# Induction_motor_control.net
KiCad netlist of a schematic drawn in EasyEDA
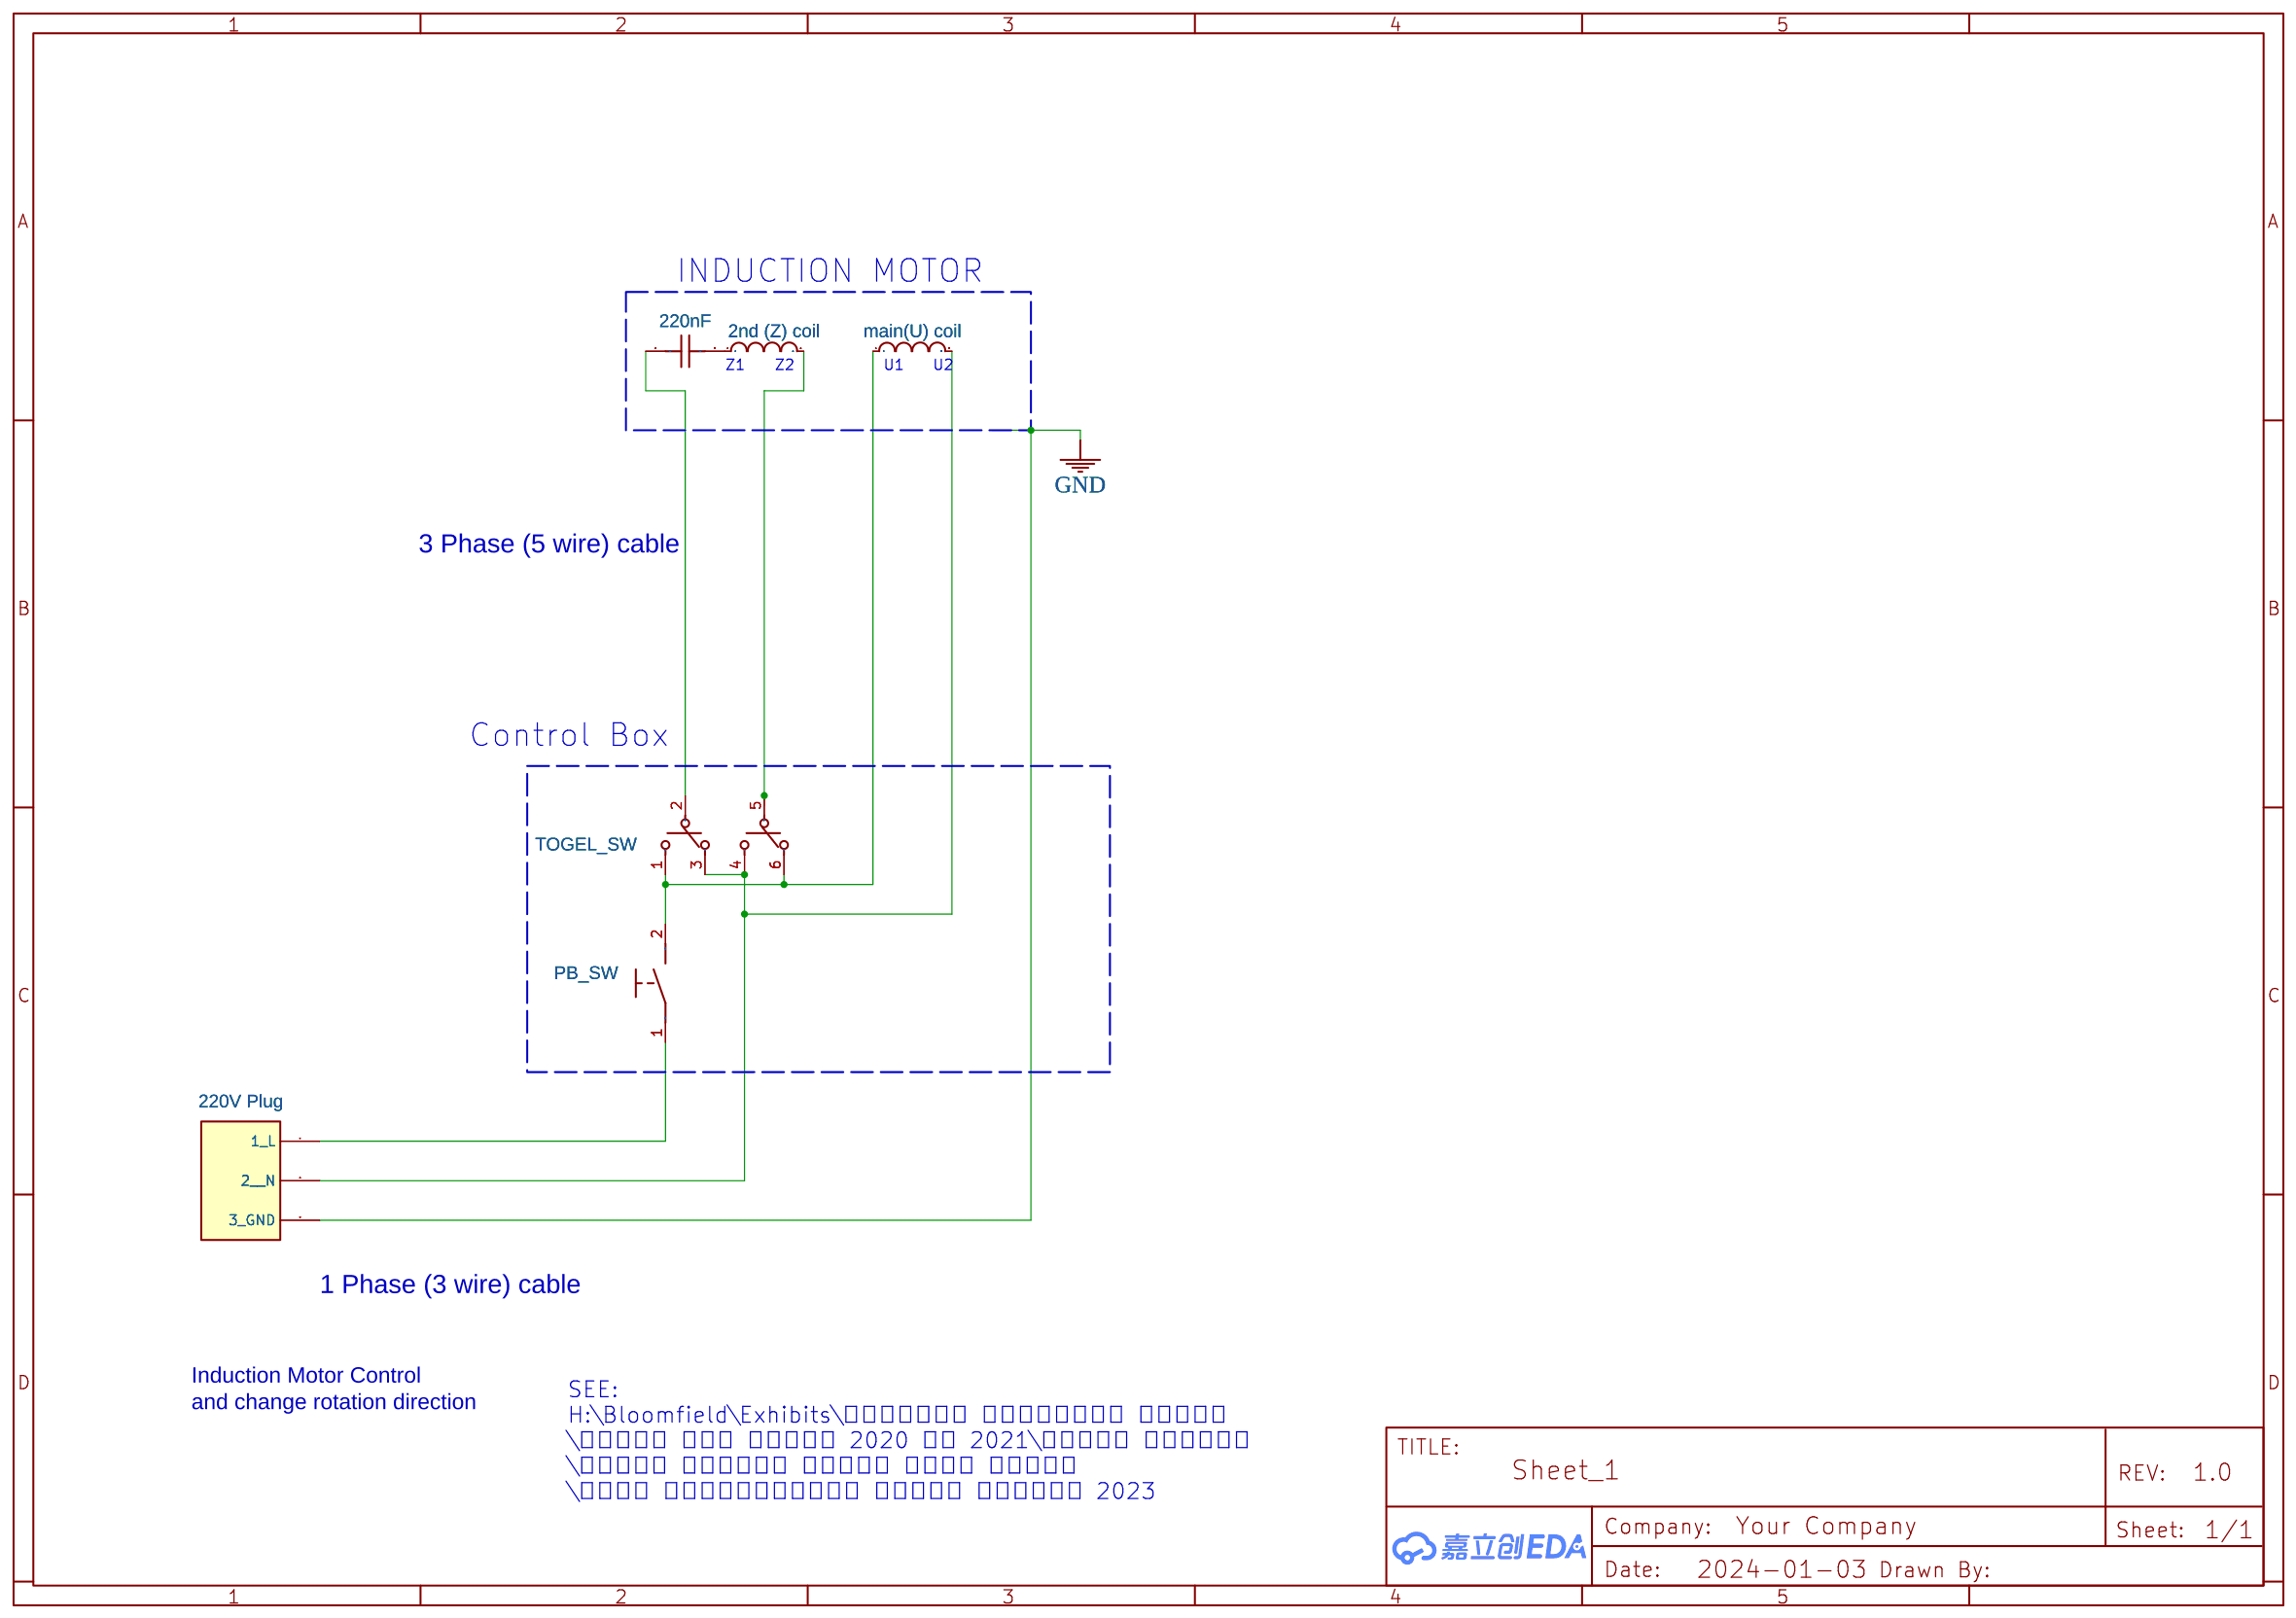
[diagram p0: schematic sheet]

(export (version "E")
  (design (tool "Eeschema 10.0.6"))
  (components
    (comp (ref "C1") (value "220nF") (libsource (lib "") (part "C_0603_US")))
    (comp (ref "L1") (value "main(U) coil") (libsource (lib "") (part "L0603_US")))
    (comp (ref "L2") (value "2nd (Z) coil") (libsource (lib "") (part "L0603_US")))
    (comp (ref "P1")
      (value "220V Plug")
      (fields (field (name "BOM_Supplier Part") "C49661"))
      (libsource (lib "") (part "Main voltage"))
    )
    (comp (ref "PB_SW")
      (value "K12C15N")
      (fields (field (name "Manufacturer") "C&K"))
      (libsource (lib "") (part "K12C15N"))
    )
    (comp (ref "SW3")
      (value "TOGEL_SW")
      (fields
        (field (name "Manufacturer Part") "2MD3T1B1M2QES-5")
        (field (name "Manufacturer") "Dailywell(德利威)")
      )
      (libsource (lib "") (part "2MD3T1B1M2QES-5"))
    )
  )
  (nets
    (net (code "1") (name "GND") (class "Default")
      (node (ref "P1") (pin "2") (pinfunction "3_GND_2") (pintype "input"))
    )
    (net (code "2") (name "Net-(C1-Pad1)") (class "Default")
      (node (ref "C1") (pin "1") (pinfunction "1_1") (pintype "unspecified"))
      (node (ref "SW3") (pin "2") (pinfunction "2_2") (pintype "unspecified"))
    )
    (net (code "3") (name "Net-(C1-Pad2)") (class "Default")
      (node (ref "C1") (pin "2") (pinfunction "2_2") (pintype "unspecified"))
      (node (ref "L2") (pin "1") (pinfunction "1_1") (pintype "unspecified"))
    )
    (net (code "4") (name "Net-(L1-Pad1)") (class "Default")
      (node (ref "L1") (pin "1") (pinfunction "1_1") (pintype "unspecified"))
      (node (ref "PB_SW") (pin "2") (pinfunction "2_2") (pintype "unspecified"))
      (node (ref "SW3") (pin "1") (pinfunction "1_1") (pintype "unspecified"))
      (node (ref "SW3") (pin "6") (pinfunction "6_6") (pintype "unspecified"))
    )
    (net (code "5") (name "Net-(L2-Pad2)") (class "Default")
      (node (ref "L2") (pin "2") (pinfunction "2_2") (pintype "unspecified"))
      (node (ref "SW3") (pin "5") (pinfunction "5_5") (pintype "unspecified"))
    )
    (net (code "6") (name "Net-(P1-1_L)") (class "Default")
      (node (ref "P1") (pin "1") (pinfunction "1_L_1") (pintype "input"))
      (node (ref "PB_SW") (pin "1") (pinfunction "1_1") (pintype "unspecified"))
    )
    (net (code "7") (name "Net-(P1-2__N)") (class "Default")
      (node (ref "L1") (pin "2") (pinfunction "2_2") (pintype "unspecified"))
      (node (ref "P1") (pin "2") (pinfunction "2__N_2") (pintype "input"))
      (node (ref "SW3") (pin "3") (pinfunction "3_3") (pintype "unspecified"))
      (node (ref "SW3") (pin "4") (pinfunction "4_4") (pintype "unspecified"))
    )
  )
)
